# Microcontroller.net
KiCad netlist of a schematic drawn in Altium Designer
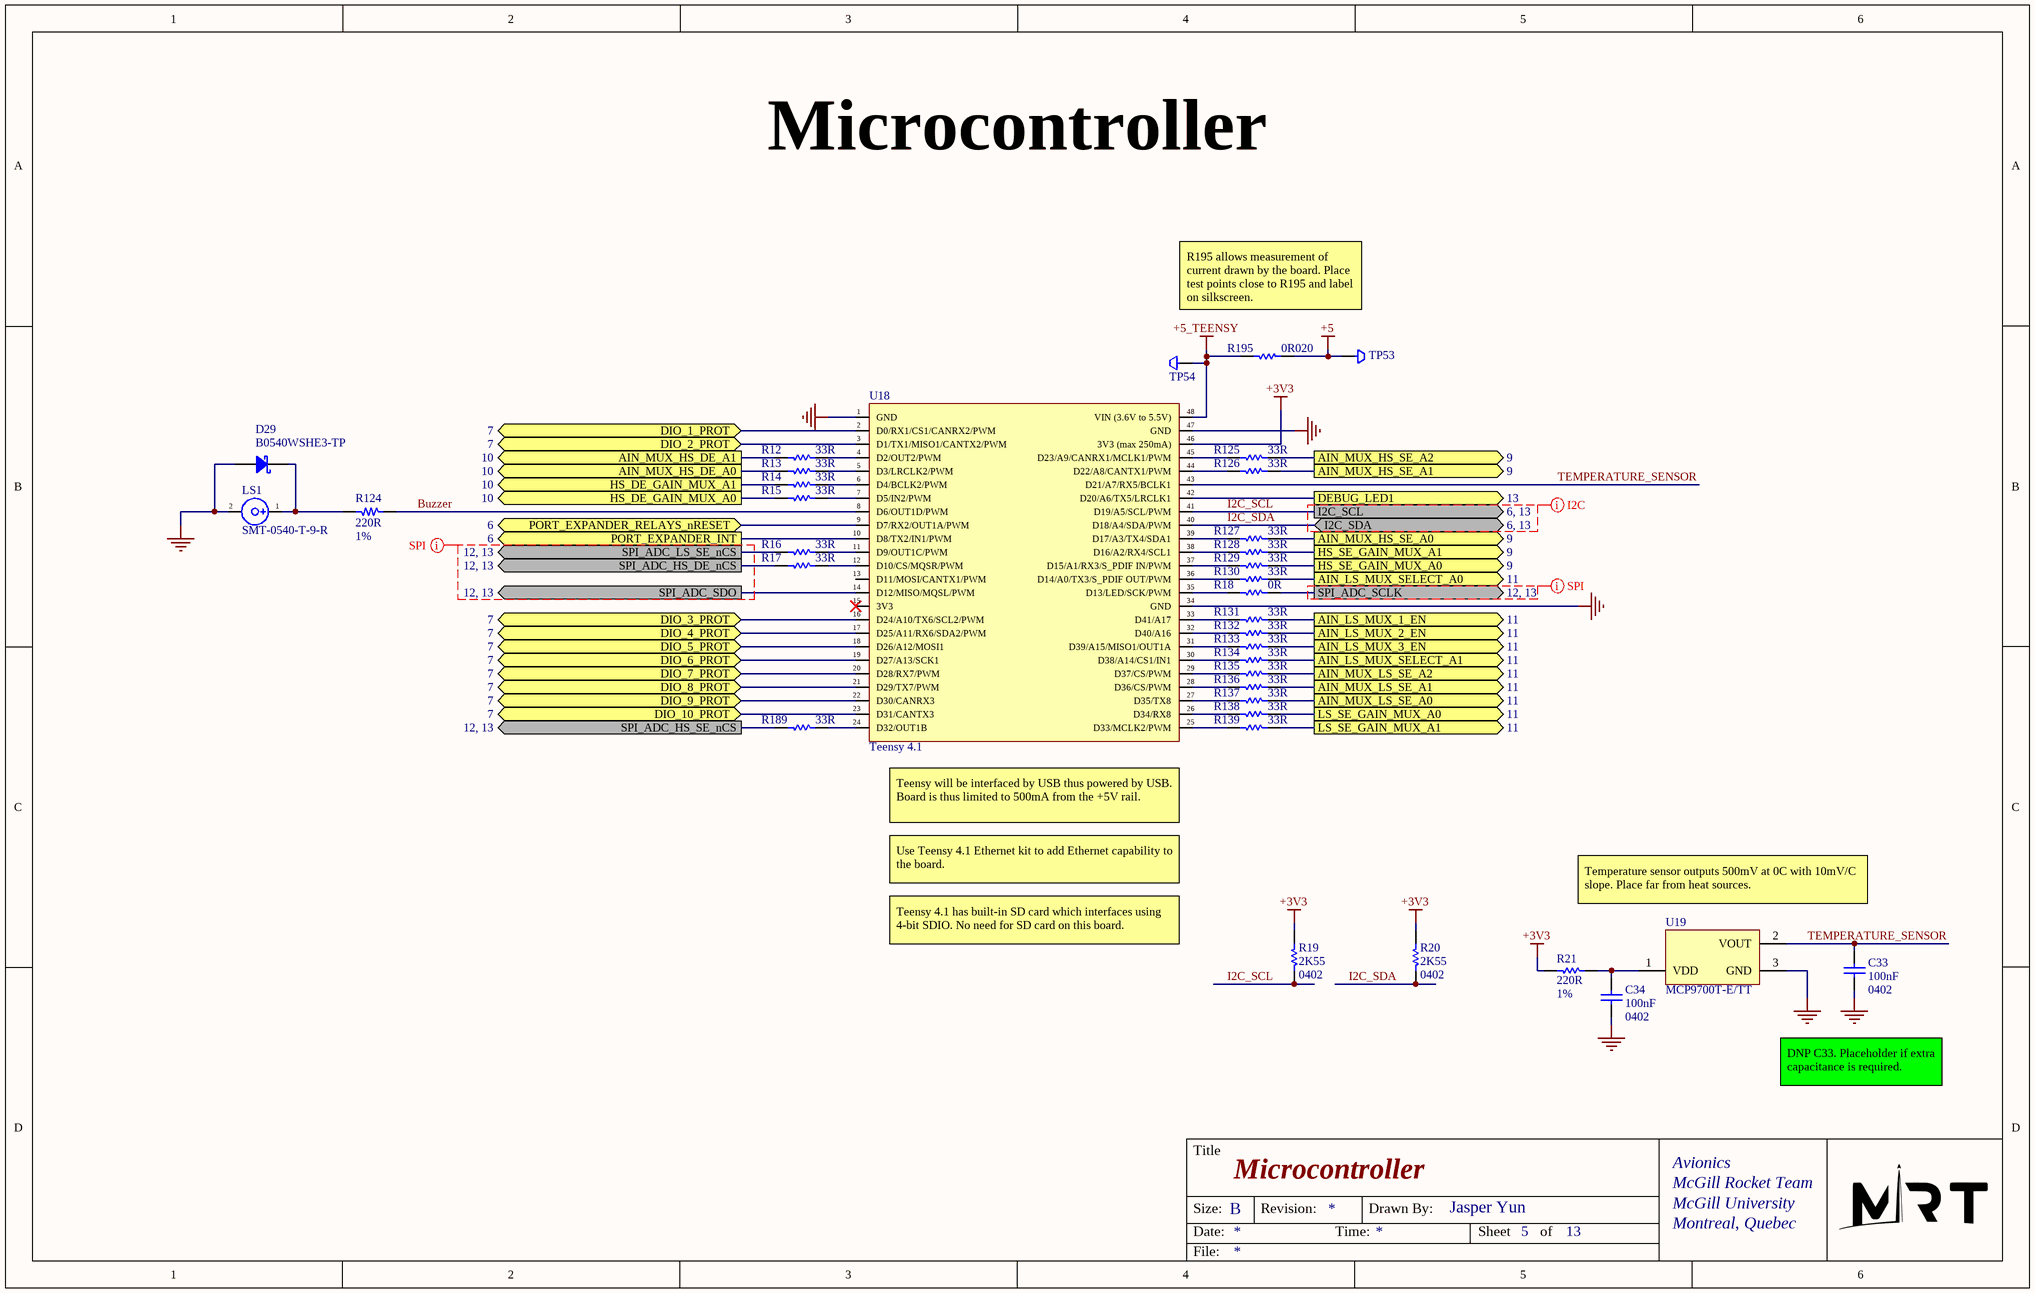
[diagram p0: Microcontroller.SchDoc]

(export (version "E")
  (design (tool "Eeschema 10.0.6"))
  (components
    (comp (ref "C33")
      (value "100nF")
      (footprint "0402 CAP")
      (description "Capacitor")
      (fields (field (name "ALTIUM_VALUE") "0402") (field (name "PUBLISHER") "Altium Limited"))
      (libsource (lib "Miscellaneous Devices") (part "Cap"))
    )
    (comp (ref "C34")
      (value "100nF")
      (footprint "0402 CAP")
      (description "Capacitor")
      (fields (field (name "ALTIUM_VALUE") "0402") (field (name "PUBLISHER") "Altium Limited"))
      (libsource (lib "Miscellaneous Devices") (part "Cap"))
    )
    (comp (ref "D29")
      (value "B0540WSHE3-TP")
      (footprint "Diode SOD323-F")
      (description "Generic Schottky Diode")
      (libsource (lib "MRT SCH Library") (part "Diode Schottky"))
    )
    (comp (ref "LS1")
      (value "SMT-0540-T-9-R")
      (footprint "Buzzer SMT-0540-T-9-R")
      (description "CMT-9648-85T\r\nMagnetic buzzer")
      (libsource (lib "MRT SCH Library") (part "Buzzer HNB09A05"))
    )
    (comp (ref "R12")
      (value "33R")
      (footprint "0402 RES")
      (description "Resistor")
      (fields (field (name "PUBLISHER") "Altium Limited"))
      (libsource (lib "Miscellaneous Devices") (part "Res1"))
    )
    (comp (ref "R13")
      (value "33R")
      (footprint "0402 RES")
      (description "Resistor")
      (fields (field (name "PUBLISHER") "Altium Limited"))
      (libsource (lib "Miscellaneous Devices") (part "Res1"))
    )
    (comp (ref "R14")
      (value "33R")
      (footprint "0402 RES")
      (description "Resistor")
      (fields (field (name "PUBLISHER") "Altium Limited"))
      (libsource (lib "Miscellaneous Devices") (part "Res1"))
    )
    (comp (ref "R15")
      (value "33R")
      (footprint "0402 RES")
      (description "Resistor")
      (fields (field (name "PUBLISHER") "Altium Limited"))
      (libsource (lib "Miscellaneous Devices") (part "Res1"))
    )
    (comp (ref "R16")
      (value "33R")
      (footprint "0402 RES")
      (description "Resistor")
      (fields (field (name "PUBLISHER") "Altium Limited"))
      (libsource (lib "Miscellaneous Devices") (part "Res1"))
    )
    (comp (ref "R17")
      (value "33R")
      (footprint "0402 RES")
      (description "Resistor")
      (fields (field (name "PUBLISHER") "Altium Limited"))
      (libsource (lib "Miscellaneous Devices") (part "Res1"))
    )
    (comp (ref "R18")
      (value "0R")
      (footprint "0402 RES")
      (description "Resistor")
      (fields (field (name "PUBLISHER") "Altium Limited"))
      (libsource (lib "Miscellaneous Devices") (part "Res1"))
    )
    (comp (ref "R19")
      (value "2K55")
      (footprint "0402 RES")
      (description "Resistor")
      (fields (field (name "ALTIUM_VALUE") "0402") (field (name "PUBLISHER") "Altium Limited"))
      (libsource (lib "Miscellaneous Devices") (part "Res1"))
    )
    (comp (ref "R20")
      (value "2K55")
      (footprint "0402 RES")
      (description "Resistor")
      (fields (field (name "ALTIUM_VALUE") "0402") (field (name "PUBLISHER") "Altium Limited"))
      (libsource (lib "Miscellaneous Devices") (part "Res1"))
    )
    (comp (ref "R21")
      (value "220R")
      (footprint "0402 RES")
      (description "Resistor")
      (fields (field (name "ALTIUM_VALUE") "1%") (field (name "PUBLISHER") "Altium Limited"))
      (libsource (lib "Miscellaneous Devices") (part "Res1"))
    )
    (comp (ref "R124")
      (value "220R")
      (footprint "0402 RES")
      (description "Generic resistor")
      (fields (field (name "TOLERANCE") "1%"))
      (libsource (lib "MRT SCH Library") (part "Resistor"))
    )
    (comp (ref "R125")
      (value "33R")
      (footprint "0402 RES")
      (description "Resistor")
      (fields (field (name "PUBLISHER") "Altium Limited"))
      (libsource (lib "Miscellaneous Devices") (part "Res1"))
    )
    (comp (ref "R126")
      (value "33R")
      (footprint "0402 RES")
      (description "Resistor")
      (fields (field (name "PUBLISHER") "Altium Limited"))
      (libsource (lib "Miscellaneous Devices") (part "Res1"))
    )
    (comp (ref "R127")
      (value "33R")
      (footprint "0402 RES")
      (description "Resistor")
      (fields (field (name "PUBLISHER") "Altium Limited"))
      (libsource (lib "Miscellaneous Devices") (part "Res1"))
    )
    (comp (ref "R128")
      (value "33R")
      (footprint "0402 RES")
      (description "Resistor")
      (fields (field (name "PUBLISHER") "Altium Limited"))
      (libsource (lib "Miscellaneous Devices") (part "Res1"))
    )
    (comp (ref "R129")
      (value "33R")
      (footprint "0402 RES")
      (description "Resistor")
      (fields (field (name "PUBLISHER") "Altium Limited"))
      (libsource (lib "Miscellaneous Devices") (part "Res1"))
    )
    (comp (ref "R130")
      (value "33R")
      (footprint "0402 RES")
      (description "Resistor")
      (fields (field (name "PUBLISHER") "Altium Limited"))
      (libsource (lib "Miscellaneous Devices") (part "Res1"))
    )
    (comp (ref "R131")
      (value "33R")
      (footprint "0402 RES")
      (description "Resistor")
      (fields (field (name "PUBLISHER") "Altium Limited"))
      (libsource (lib "Miscellaneous Devices") (part "Res1"))
    )
    (comp (ref "R132")
      (value "33R")
      (footprint "0402 RES")
      (description "Resistor")
      (fields (field (name "PUBLISHER") "Altium Limited"))
      (libsource (lib "Miscellaneous Devices") (part "Res1"))
    )
    (comp (ref "R133")
      (value "33R")
      (footprint "0402 RES")
      (description "Resistor")
      (fields (field (name "PUBLISHER") "Altium Limited"))
      (libsource (lib "Miscellaneous Devices") (part "Res1"))
    )
    (comp (ref "R134")
      (value "33R")
      (footprint "0402 RES")
      (description "Resistor")
      (fields (field (name "PUBLISHER") "Altium Limited"))
      (libsource (lib "Miscellaneous Devices") (part "Res1"))
    )
    (comp (ref "R135")
      (value "33R")
      (footprint "0402 RES")
      (description "Resistor")
      (fields (field (name "PUBLISHER") "Altium Limited"))
      (libsource (lib "Miscellaneous Devices") (part "Res1"))
    )
    (comp (ref "R136")
      (value "33R")
      (footprint "0402 RES")
      (description "Resistor")
      (fields (field (name "PUBLISHER") "Altium Limited"))
      (libsource (lib "Miscellaneous Devices") (part "Res1"))
    )
    (comp (ref "R137")
      (value "33R")
      (footprint "0402 RES")
      (description "Resistor")
      (fields (field (name "PUBLISHER") "Altium Limited"))
      (libsource (lib "Miscellaneous Devices") (part "Res1"))
    )
    (comp (ref "R138")
      (value "33R")
      (footprint "0402 RES")
      (description "Resistor")
      (fields (field (name "PUBLISHER") "Altium Limited"))
      (libsource (lib "Miscellaneous Devices") (part "Res1"))
    )
    (comp (ref "R139")
      (value "33R")
      (footprint "0402 RES")
      (description "Resistor")
      (fields (field (name "PUBLISHER") "Altium Limited"))
      (libsource (lib "Miscellaneous Devices") (part "Res1"))
    )
    (comp (ref "R189")
      (value "33R")
      (footprint "0402 RES")
      (description "Resistor")
      (fields (field (name "PUBLISHER") "Altium Limited"))
      (libsource (lib "Miscellaneous Devices") (part "Res1"))
    )
    (comp (ref "R195")
      (value "0R020")
      (footprint "0805 RES")
      (description "Resistor")
      (fields (field (name "PUBLISHER") "Altium Limited"))
      (libsource (lib "Miscellaneous Devices") (part "Res1"))
    )
    (comp (ref "TP53")
      (value "Test Point - Keystone 5015")
      (footprint "Test Point Keystone 5015")
      (description "Keystone 5015 Test point")
      (libsource (lib "MRT SCH Library") (part "Test Point - Keystone 5015"))
    )
    (comp (ref "TP54")
      (value "Test Point - Keystone 5015")
      (footprint "Test Point Keystone 5015")
      (description "Keystone 5015 Test point")
      (libsource (lib "MRT SCH Library") (part "Test Point - Keystone 5015"))
    )
    (comp (ref "U18")
      (value "Teensy 4.1")
      (footprint "Teensy 4.1")
      (description "Teensy 4.1 breakout (no ethernet or USB host pins exposed)")
      (libsource (lib "MRT SCH Library") (part "Teensy 4.1"))
    )
    (comp (ref "U19")
      (value "MCP9700T-E/TT")
      (footprint "SOT-23-TT3_M")
      (description "Low-Power Linear Active Thermistor IC, 3-Pin SOT-23, Extended Temperature, Tape and Reel")
      (libsource (lib "Altium Content Vault") (part "SEN-TEMP-MCP9700-3"))
    )
  )
  (nets
    (net (code "1") (name "+3V3") (class "Default")
      (node (ref "R19") (pin "1") (pinfunction "1_1") (pintype "passive"))
      (node (ref "R20") (pin "1") (pinfunction "1_1") (pintype "passive"))
      (node (ref "R21") (pin "1") (pinfunction "1_1") (pintype "passive"))
      (node (ref "U18") (pin "46") (pinfunction "3V3_(max_250mA)_46") (pintype "passive"))
    )
    (net (code "2") (name "+5") (class "Default")
      (node (ref "R195") (pin "2") (pinfunction "2_2") (pintype "passive"))
      (node (ref "TP53") (pin "1") (pinfunction "1_1") (pintype "passive"))
    )
    (net (code "3") (name "+5_TEENSY") (class "Default")
      (node (ref "R195") (pin "1") (pinfunction "1_1") (pintype "passive"))
      (node (ref "TP54") (pin "1") (pinfunction "1_1") (pintype "passive"))
      (node (ref "U18") (pin "48") (pinfunction "VIN_(3.6V_to_5.5V)_48") (pintype "passive"))
    )
    (net (code "4") (name "/AIN_LS_MUX_1_EN") (class "Default")
      (node (ref "R131") (pin "2") (pinfunction "2_2") (pintype "passive"))
    )
    (net (code "5") (name "/AIN_LS_MUX_2_EN") (class "Default")
      (node (ref "R132") (pin "2") (pinfunction "2_2") (pintype "passive"))
    )
    (net (code "6") (name "/AIN_LS_MUX_3_EN") (class "Default")
      (node (ref "R133") (pin "2") (pinfunction "2_2") (pintype "passive"))
    )
    (net (code "7") (name "/AIN_LS_MUX_SELECT_A0") (class "Default")
      (node (ref "R130") (pin "2") (pinfunction "2_2") (pintype "passive"))
    )
    (net (code "8") (name "/AIN_LS_MUX_SELECT_A1") (class "Default")
      (node (ref "R134") (pin "2") (pinfunction "2_2") (pintype "passive"))
    )
    (net (code "9") (name "/AIN_MUX_HS_DE_A0") (class "Default")
      (node (ref "R13") (pin "1") (pinfunction "1_1") (pintype "passive"))
    )
    (net (code "10") (name "/AIN_MUX_HS_DE_A1") (class "Default")
      (node (ref "R12") (pin "1") (pinfunction "1_1") (pintype "passive"))
    )
    (net (code "11") (name "/AIN_MUX_HS_SE_A0") (class "Default")
      (node (ref "R127") (pin "2") (pinfunction "2_2") (pintype "passive"))
    )
    (net (code "12") (name "/AIN_MUX_HS_SE_A1") (class "Default")
      (node (ref "R126") (pin "2") (pinfunction "2_2") (pintype "passive"))
    )
    (net (code "13") (name "/AIN_MUX_HS_SE_A2") (class "Default")
      (node (ref "R125") (pin "2") (pinfunction "2_2") (pintype "passive"))
    )
    (net (code "14") (name "/AIN_MUX_LS_SE_A0") (class "Default")
      (node (ref "R137") (pin "2") (pinfunction "2_2") (pintype "passive"))
    )
    (net (code "15") (name "/AIN_MUX_LS_SE_A1") (class "Default")
      (node (ref "R136") (pin "2") (pinfunction "2_2") (pintype "passive"))
    )
    (net (code "16") (name "/AIN_MUX_LS_SE_A2") (class "Default")
      (node (ref "R135") (pin "2") (pinfunction "2_2") (pintype "passive"))
    )
    (net (code "17") (name "/Buzzer") (class "Default")
      (node (ref "R124") (pin "1") (pinfunction "1_1") (pintype "passive"))
      (node (ref "U18") (pin "8") (pinfunction "D6/OUT1D/PWM_8") (pintype "passive"))
    )
    (net (code "18") (name "/DEBUG_LED1") (class "Default")
      (node (ref "U18") (pin "42") (pinfunction "D20/A6/TX5/LRCLK1_42") (pintype "passive"))
    )
    (net (code "19") (name "/DIO_1_PROT") (class "Default")
      (node (ref "U18") (pin "2") (pinfunction "D0/RX1/CS1/CANRX2/PWM_2") (pintype "passive"))
    )
    (net (code "20") (name "/DIO_2_PROT") (class "Default")
      (node (ref "U18") (pin "3") (pinfunction "D1/TX1/MISO1/CANTX2/PWM_3") (pintype "passive"))
    )
    (net (code "21") (name "/DIO_3_PROT") (class "Default")
      (node (ref "U18") (pin "16") (pinfunction "D24/A10/TX6/SCL2/PWM_16") (pintype "passive"))
    )
    (net (code "22") (name "/DIO_4_PROT") (class "Default")
      (node (ref "U18") (pin "17") (pinfunction "D25/A11/RX6/SDA2/PWM_17") (pintype "passive"))
    )
    (net (code "23") (name "/DIO_5_PROT") (class "Default")
      (node (ref "U18") (pin "18") (pinfunction "D26/A12/MOSI1_18") (pintype "passive"))
    )
    (net (code "24") (name "/DIO_6_PROT") (class "Default")
      (node (ref "U18") (pin "19") (pinfunction "D27/A13/SCK1_19") (pintype "passive"))
    )
    (net (code "25") (name "/DIO_7_PROT") (class "Default")
      (node (ref "U18") (pin "20") (pinfunction "D28/RX7/PWM_20") (pintype "passive"))
    )
    (net (code "26") (name "/DIO_8_PROT") (class "Default")
      (node (ref "U18") (pin "21") (pinfunction "D29/TX7/PWM_21") (pintype "passive"))
    )
    (net (code "27") (name "/DIO_9_PROT") (class "Default")
      (node (ref "U18") (pin "22") (pinfunction "D30/CANRX3_22") (pintype "passive"))
    )
    (net (code "28") (name "/DIO_10_PROT") (class "Default")
      (node (ref "U18") (pin "23") (pinfunction "D31/CANTX3_23") (pintype "passive"))
    )
    (net (code "29") (name "/HS_DE_GAIN_MUX_A0") (class "Default")
      (node (ref "R15") (pin "1") (pinfunction "1_1") (pintype "passive"))
    )
    (net (code "30") (name "/HS_DE_GAIN_MUX_A1") (class "Default")
      (node (ref "R14") (pin "1") (pinfunction "1_1") (pintype "passive"))
    )
    (net (code "31") (name "/HS_SE_GAIN_MUX_A0") (class "Default")
      (node (ref "R129") (pin "2") (pinfunction "2_2") (pintype "passive"))
    )
    (net (code "32") (name "/HS_SE_GAIN_MUX_A1") (class "Default")
      (node (ref "R128") (pin "2") (pinfunction "2_2") (pintype "passive"))
    )
    (net (code "33") (name "/I2C_SCL") (class "Default")
      (node (ref "R19") (pin "2") (pinfunction "2_2") (pintype "passive"))
      (node (ref "U18") (pin "41") (pinfunction "D19/A5/SCL/PWM_41") (pintype "passive"))
    )
    (net (code "34") (name "/I2C_SDA") (class "Default")
      (node (ref "R20") (pin "2") (pinfunction "2_2") (pintype "passive"))
      (node (ref "U18") (pin "40") (pinfunction "D18/A4/SDA/PWM_40") (pintype "passive"))
    )
    (net (code "35") (name "/LS_SE_GAIN_MUX_A0") (class "Default")
      (node (ref "R138") (pin "2") (pinfunction "2_2") (pintype "passive"))
    )
    (net (code "36") (name "/LS_SE_GAIN_MUX_A1") (class "Default")
      (node (ref "R139") (pin "2") (pinfunction "2_2") (pintype "passive"))
    )
    (net (code "37") (name "/PORT_EXPANDER_INT") (class "Default")
      (node (ref "U18") (pin "10") (pinfunction "D8/TX2/IN1/PWM_10") (pintype "passive"))
    )
    (net (code "38") (name "/PORT_EXPANDER_RELAYS_nRESET") (class "Default")
      (node (ref "U18") (pin "9") (pinfunction "D7/RX2/OUT1A/PWM_9") (pintype "passive"))
    )
    (net (code "39") (name "/SPI_ADC_HS_DE_nCS") (class "Default")
      (node (ref "R17") (pin "1") (pinfunction "1_1") (pintype "passive"))
    )
    (net (code "40") (name "/SPI_ADC_HS_SE_nCS") (class "Default")
      (node (ref "R189") (pin "1") (pinfunction "1_1") (pintype "passive"))
    )
    (net (code "41") (name "/SPI_ADC_LS_SE_nCS") (class "Default")
      (node (ref "R16") (pin "1") (pinfunction "1_1") (pintype "passive"))
    )
    (net (code "42") (name "/SPI_ADC_SCLK") (class "Default")
      (node (ref "R18") (pin "2") (pinfunction "2_2") (pintype "passive"))
    )
    (net (code "43") (name "/SPI_ADC_SDO") (class "Default")
      (node (ref "U18") (pin "14") (pinfunction "D12/MISO/MQSL/PWM_14") (pintype "passive"))
    )
    (net (code "44") (name "/TEMPERATURE_SENSOR") (class "Default")
      (node (ref "C33") (pin "2") (pinfunction "2_2") (pintype "passive"))
      (node (ref "U18") (pin "43") (pinfunction "D21/A7/RX5/BCLK1_43") (pintype "passive"))
      (node (ref "U19") (pin "2") (pinfunction "VOUT_2") (pintype "power_in"))
    )
    (net (code "45") (name "GND") (class "Default")
      (node (ref "C33") (pin "1") (pinfunction "1_1") (pintype "passive"))
      (node (ref "C34") (pin "1") (pinfunction "1_1") (pintype "passive"))
      (node (ref "D29") (pin "1") (pinfunction "1_1") (pintype "passive"))
      (node (ref "LS1") (pin "2") (pinfunction "K_2") (pintype "passive"))
      (node (ref "U18") (pin "1") (pinfunction "GND_1") (pintype "passive"))
      (node (ref "U18") (pin "34") (pinfunction "GND_34") (pintype "passive"))
      (node (ref "U18") (pin "47") (pinfunction "GND_47") (pintype "passive"))
      (node (ref "U19") (pin "3") (pinfunction "GND_3") (pintype "power_in"))
    )
    (net (code "46") (name "Net-(LS1-A)") (class "Default")
      (node (ref "D29") (pin "2") (pinfunction "2_2") (pintype "passive"))
      (node (ref "LS1") (pin "1") (pinfunction "A_1") (pintype "passive"))
      (node (ref "R124") (pin "2") (pinfunction "2_2") (pintype "passive"))
    )
    (net (code "47") (name "Net-(U18-D2{slash}OUT2{slash}PWM)") (class "Default")
      (node (ref "R12") (pin "2") (pinfunction "2_2") (pintype "passive"))
      (node (ref "U18") (pin "4") (pinfunction "D2/OUT2/PWM_4") (pintype "passive"))
    )
    (net (code "48") (name "Net-(U18-D3{slash}LRCLK2{slash}PWM)") (class "Default")
      (node (ref "R13") (pin "2") (pinfunction "2_2") (pintype "passive"))
      (node (ref "U18") (pin "5") (pinfunction "D3/LRCLK2/PWM_5") (pintype "passive"))
    )
    (net (code "49") (name "Net-(U18-D4{slash}BCLK2{slash}PWM)") (class "Default")
      (node (ref "R14") (pin "2") (pinfunction "2_2") (pintype "passive"))
      (node (ref "U18") (pin "6") (pinfunction "D4/BCLK2/PWM_6") (pintype "passive"))
    )
    (net (code "50") (name "Net-(U18-D5{slash}IN2{slash}PWM)") (class "Default")
      (node (ref "R15") (pin "2") (pinfunction "2_2") (pintype "passive"))
      (node (ref "U18") (pin "7") (pinfunction "D5/IN2/PWM_7") (pintype "passive"))
    )
    (net (code "51") (name "Net-(U18-D9{slash}OUT1C{slash}PWM)") (class "Default")
      (node (ref "R16") (pin "2") (pinfunction "2_2") (pintype "passive"))
      (node (ref "U18") (pin "11") (pinfunction "D9/OUT1C/PWM_11") (pintype "passive"))
    )
    (net (code "52") (name "Net-(U18-D10{slash}CS{slash}MQSR{slash}PWM)") (class "Default")
      (node (ref "R17") (pin "2") (pinfunction "2_2") (pintype "passive"))
      (node (ref "U18") (pin "12") (pinfunction "D10/CS/MQSR/PWM_12") (pintype "passive"))
    )
    (net (code "53") (name "Net-(U18-D13{slash}LED{slash}SCK{slash}PWM)") (class "Default")
      (node (ref "R18") (pin "1") (pinfunction "1_1") (pintype "passive"))
      (node (ref "U18") (pin "35") (pinfunction "D13/LED/SCK/PWM_35") (pintype "passive"))
    )
    (net (code "54") (name "Net-(U18-D14{slash}A0{slash}TX3{slash}S_PDIF_OUT{slash}PWM)") (class "Default")
      (node (ref "R130") (pin "1") (pinfunction "1_1") (pintype "passive"))
      (node (ref "U18") (pin "36") (pinfunction "D14/A0/TX3/S_PDIF_OUT/PWM_36") (pintype "passive"))
    )
    (net (code "55") (name "Net-(U18-D15{slash}A1{slash}RX3{slash}S_PDIF_IN{slash}PWM)") (class "Default")
      (node (ref "R129") (pin "1") (pinfunction "1_1") (pintype "passive"))
      (node (ref "U18") (pin "37") (pinfunction "D15/A1/RX3/S_PDIF_IN/PWM_37") (pintype "passive"))
    )
    (net (code "56") (name "Net-(U18-D16{slash}A2{slash}RX4{slash}SCL1)") (class "Default")
      (node (ref "R128") (pin "1") (pinfunction "1_1") (pintype "passive"))
      (node (ref "U18") (pin "38") (pinfunction "D16/A2/RX4/SCL1_38") (pintype "passive"))
    )
    (net (code "57") (name "Net-(U18-D17{slash}A3{slash}TX4{slash}SDA1)") (class "Default")
      (node (ref "R127") (pin "1") (pinfunction "1_1") (pintype "passive"))
      (node (ref "U18") (pin "39") (pinfunction "D17/A3/TX4/SDA1_39") (pintype "passive"))
    )
    (net (code "58") (name "Net-(U18-D22{slash}A8{slash}CANTX1{slash}PWM)") (class "Default")
      (node (ref "R126") (pin "1") (pinfunction "1_1") (pintype "passive"))
      (node (ref "U18") (pin "44") (pinfunction "D22/A8/CANTX1/PWM_44") (pintype "passive"))
    )
    (net (code "59") (name "Net-(U18-D23{slash}A9{slash}CANRX1{slash}MCLK1{slash}PWM)") (class "Default")
      (node (ref "R125") (pin "1") (pinfunction "1_1") (pintype "passive"))
      (node (ref "U18") (pin "45") (pinfunction "D23/A9/CANRX1/MCLK1/PWM_45") (pintype "passive"))
    )
    (net (code "60") (name "Net-(U18-D32{slash}OUT1B)") (class "Default")
      (node (ref "R189") (pin "2") (pinfunction "2_2") (pintype "passive"))
      (node (ref "U18") (pin "24") (pinfunction "D32/OUT1B_24") (pintype "passive"))
    )
    (net (code "61") (name "Net-(U18-D33{slash}MCLK2{slash}PWM)") (class "Default")
      (node (ref "R139") (pin "1") (pinfunction "1_1") (pintype "passive"))
      (node (ref "U18") (pin "25") (pinfunction "D33/MCLK2/PWM_25") (pintype "passive"))
    )
    (net (code "62") (name "Net-(U18-D34{slash}RX8)") (class "Default")
      (node (ref "R138") (pin "1") (pinfunction "1_1") (pintype "passive"))
      (node (ref "U18") (pin "26") (pinfunction "D34/RX8_26") (pintype "passive"))
    )
    (net (code "63") (name "Net-(U18-D35{slash}TX8)") (class "Default")
      (node (ref "R137") (pin "1") (pinfunction "1_1") (pintype "passive"))
      (node (ref "U18") (pin "27") (pinfunction "D35/TX8_27") (pintype "passive"))
    )
    (net (code "64") (name "Net-(U18-D36{slash}CS{slash}PWM)") (class "Default")
      (node (ref "R136") (pin "1") (pinfunction "1_1") (pintype "passive"))
      (node (ref "U18") (pin "28") (pinfunction "D36/CS/PWM_28") (pintype "passive"))
    )
    (net (code "65") (name "Net-(U18-D37{slash}CS{slash}PWM)") (class "Default")
      (node (ref "R135") (pin "1") (pinfunction "1_1") (pintype "passive"))
      (node (ref "U18") (pin "29") (pinfunction "D37/CS/PWM_29") (pintype "passive"))
    )
    (net (code "66") (name "Net-(U18-D38{slash}A14{slash}CS1{slash}IN1)") (class "Default")
      (node (ref "R134") (pin "1") (pinfunction "1_1") (pintype "passive"))
      (node (ref "U18") (pin "30") (pinfunction "D38/A14/CS1/IN1_30") (pintype "passive"))
    )
    (net (code "67") (name "Net-(U18-D39{slash}A15{slash}MISO1{slash}OUT1A)") (class "Default")
      (node (ref "R133") (pin "1") (pinfunction "1_1") (pintype "passive"))
      (node (ref "U18") (pin "31") (pinfunction "D39/A15/MISO1/OUT1A_31") (pintype "passive"))
    )
    (net (code "68") (name "Net-(U18-D40{slash}A16)") (class "Default")
      (node (ref "R132") (pin "1") (pinfunction "1_1") (pintype "passive"))
      (node (ref "U18") (pin "32") (pinfunction "D40/A16_32") (pintype "passive"))
    )
    (net (code "69") (name "Net-(U18-D41{slash}A17)") (class "Default")
      (node (ref "R131") (pin "1") (pinfunction "1_1") (pintype "passive"))
      (node (ref "U18") (pin "33") (pinfunction "D41/A17_33") (pintype "passive"))
    )
    (net (code "70") (name "Net-(U19-VDD)") (class "Default")
      (node (ref "C34") (pin "2") (pinfunction "2_2") (pintype "passive"))
      (node (ref "R21") (pin "2") (pinfunction "2_2") (pintype "passive"))
      (node (ref "U19") (pin "1") (pinfunction "VDD_1") (pintype "power_in"))
    )
    (net (code "71") (name "unconnected-(U18-3V3-Pad15)") (class "Default")
      (node (ref "U18") (pin "15") (pinfunction "3V3_15") (pintype "passive+no_connect"))
    )
    (net (code "72") (name "unconnected-(U18-D11{slash}MOSI{slash}CANTX1{slash}PWM-Pad13)") (class "Default")
      (node (ref "U18") (pin "13") (pinfunction "D11/MOSI/CANTX1/PWM_13") (pintype "passive"))
    )
  )
)
